# 01-ORIN_PWR.net
KiCad netlist of a schematic drawn in Altium Designer
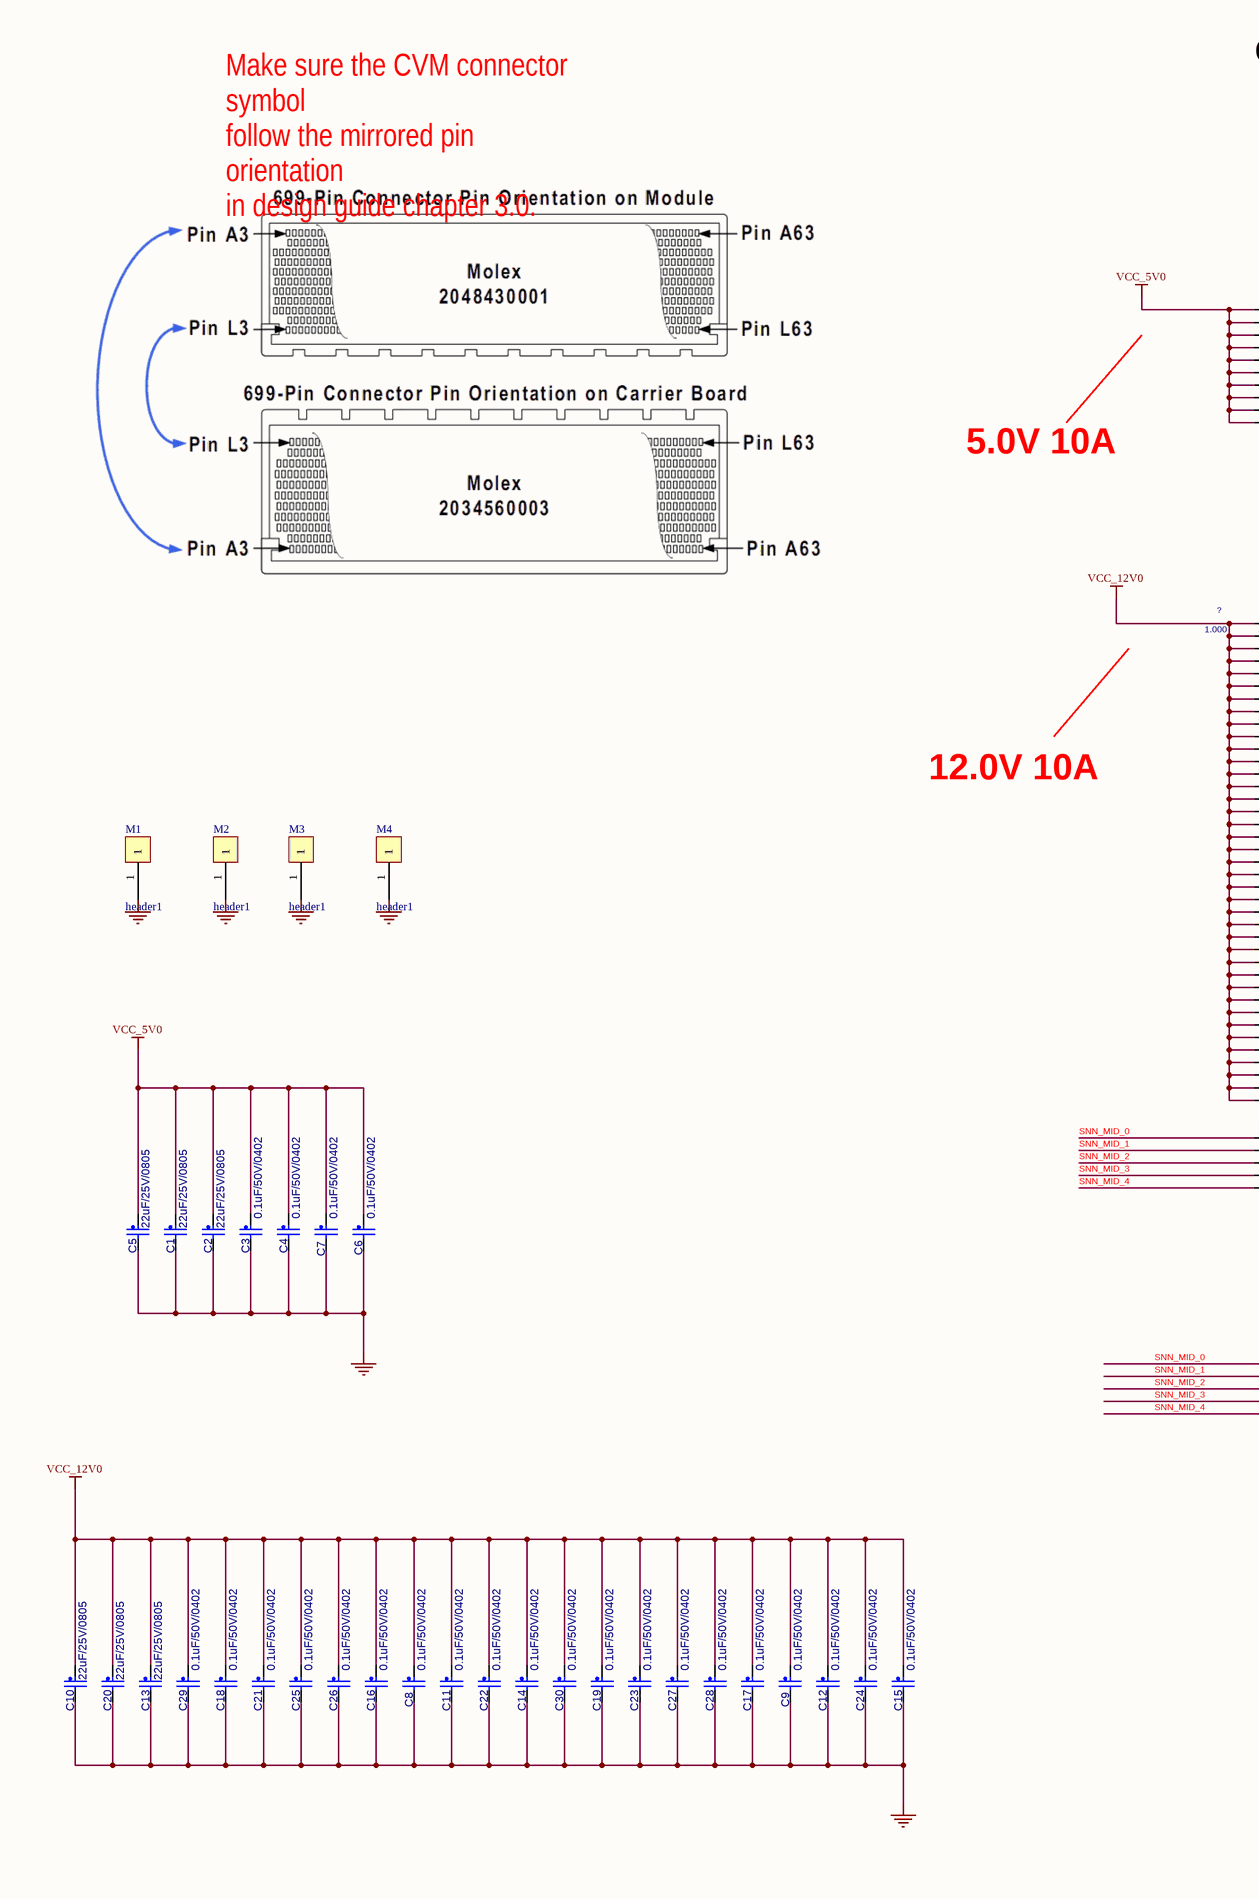
[diagram p0: 01-ORIN_PWR.SchDoc, left]
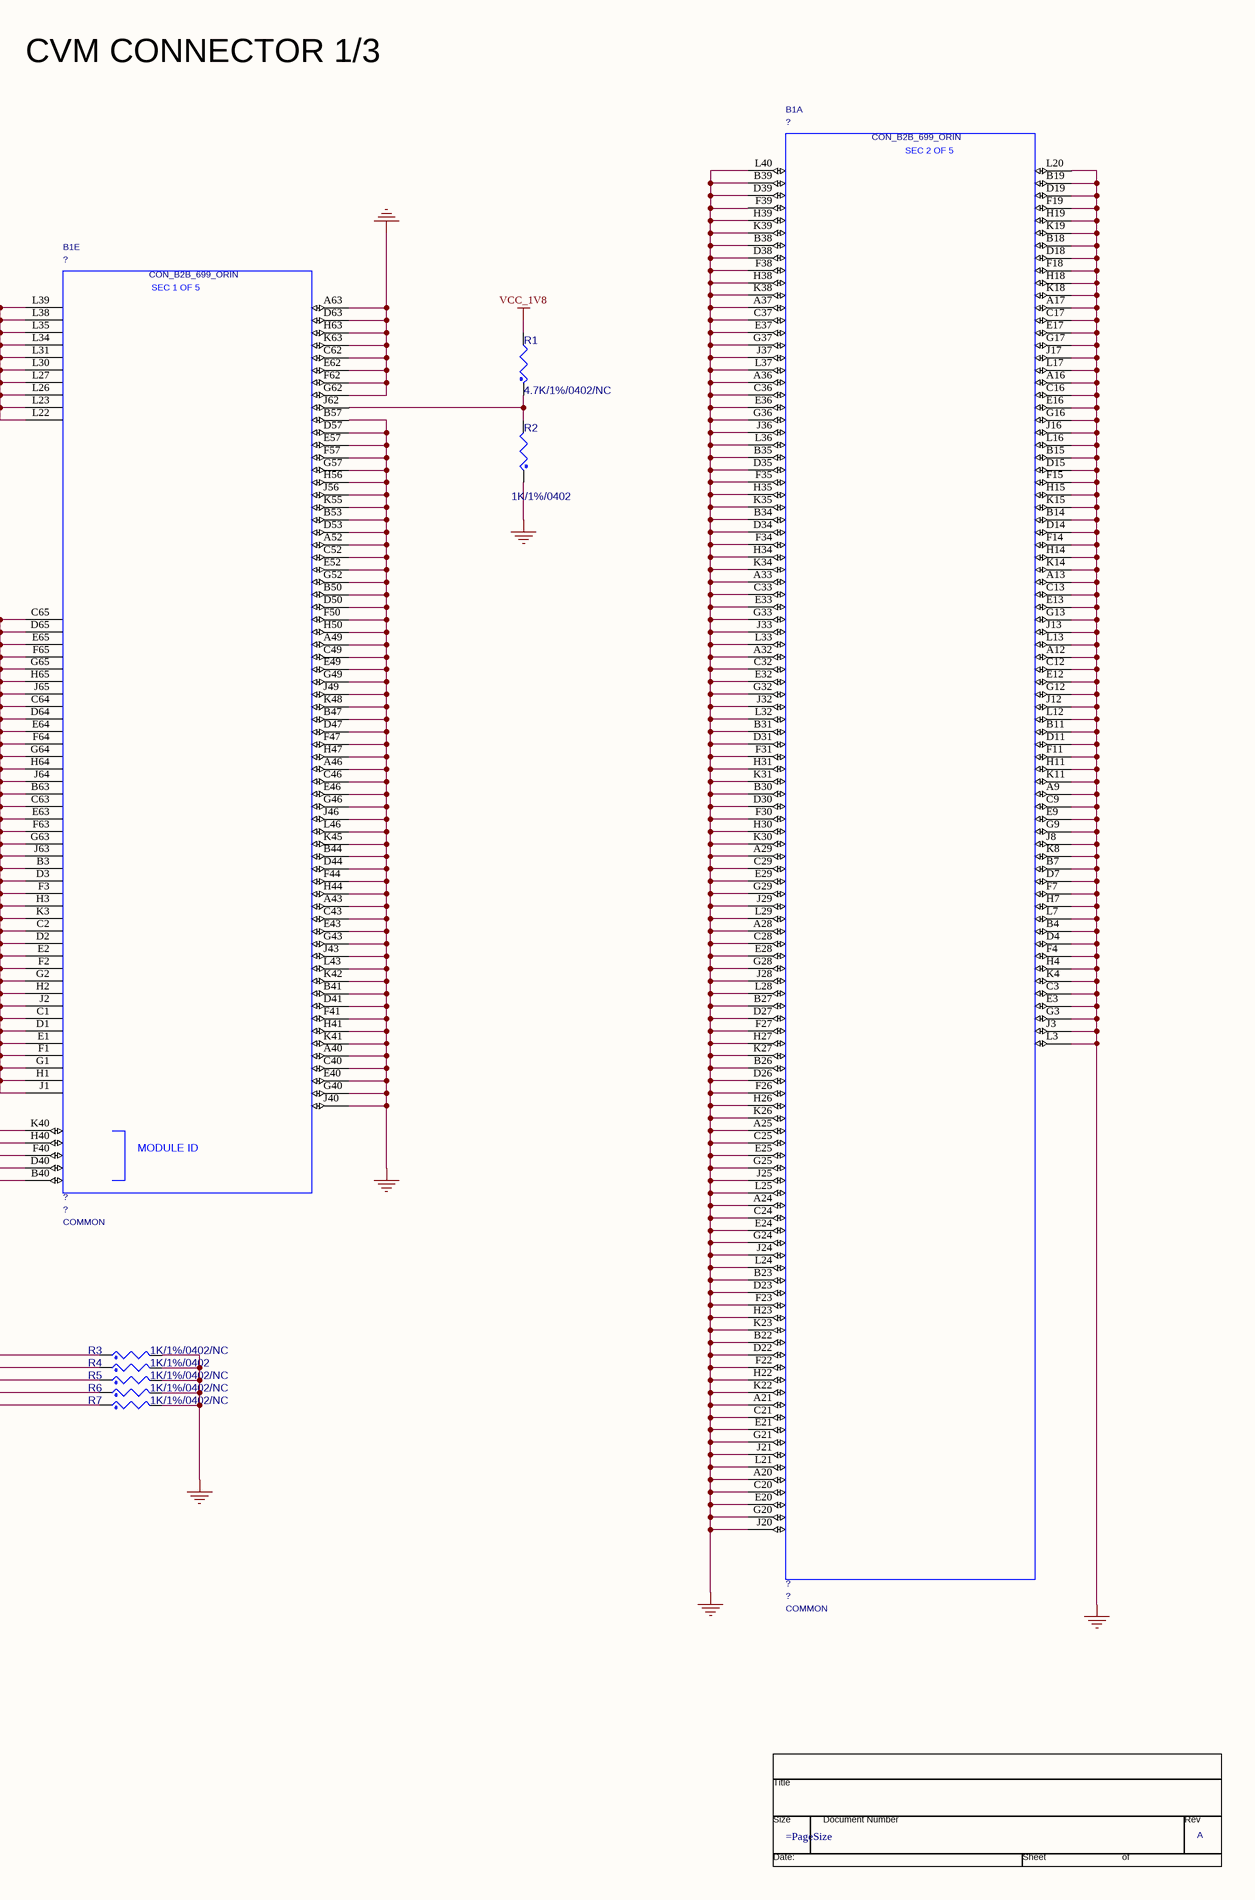
[diagram p1: 01-ORIN_PWR.SchDoc, right]

(export (version "E")
  (design (tool "Eeschema 10.0.6"))
  (components
    (comp (ref "B1")
      (value "CON_B2B_699_ORIN")
      (footprint "CON_MIRMEZ_699_BGA_ST_P009_P013_P015_REVERSE")
      (description "2034560003/MOLEX")
      (fields
        (field (name "DEVICE") "CON_B2B_699_ORIN")
        (field (name "NV_PN") "?")
        (field (name "PACK_TYPE") "?")
        (field (name "PATH") "?")
        (field (name "SKU") "COMMON")
      )
      (libsource (lib "*") (part "CON_B2B_699"))
    )
    (comp (ref "C1")
      (value "22uF/25V/0805")
      (footprint "C0805")
      (description "GRT31CC71E226ME13/MURATA")
      (fields (field (name "TOLERANCE") "10%") (field (name "VOLTAGE") "10v"))
      (libsource (lib "*") (part "CAP_NP"))
    )
    (comp (ref "C2")
      (value "22uF/25V/0805")
      (footprint "C0805")
      (description "GRT31CC71E226ME13/MURATA")
      (fields (field (name "VOLTAGE") "10v") (field (name "TOLERANCE") "10%"))
      (libsource (lib "*") (part "CAP_NP"))
    )
    (comp (ref "C3")
      (value "0.1uF/50V/0402")
      (footprint "C0402")
      (description "GCM155R71H104KE02/MURATA")
      (fields (field (name "VOLTAGE") "16V") (field (name "TOLERANCE") "10%"))
      (libsource (lib "*") (part "CAP_NP"))
    )
    (comp (ref "C4")
      (value "0.1uF/50V/0402")
      (footprint "C0402")
      (description "GCM155R71H104KE02/MURATA")
      (fields (field (name "TOLERANCE") "10%") (field (name "VOLTAGE") "16V"))
      (libsource (lib "*") (part "CAP_NP"))
    )
    (comp (ref "C5")
      (value "22uF/25V/0805")
      (footprint "C0805")
      (description "GRT31CC71E226ME13/MURATA")
      (fields (field (name "TOLERANCE") "10%") (field (name "VOLTAGE") "10v"))
      (libsource (lib "*") (part "CAP_NP"))
    )
    (comp (ref "C6")
      (value "0.1uF/50V/0402")
      (footprint "C0402")
      (description "GCM155R71H104KE02/MURATA")
      (fields (field (name "TOLERANCE") "10%") (field (name "VOLTAGE") "16V"))
      (libsource (lib "*") (part "CAP_NP"))
    )
    (comp (ref "C7")
      (value "0.1uF/50V/0402")
      (footprint "C0402")
      (description "GCM155R71H104KE02/MURATA")
      (fields (field (name "VOLTAGE") "16V") (field (name "TOLERANCE") "10%"))
      (libsource (lib "*") (part "CAP_NP"))
    )
    (comp (ref "C8")
      (value "0.1uF/50V/0402")
      (footprint "C0402")
      (description "GCM155R71H104KE02/MURATA")
      (fields (field (name "TOLERANCE") "10%") (field (name "VOLTAGE") "16V"))
      (libsource (lib "*") (part "CAP_NP"))
    )
    (comp (ref "C9")
      (value "0.1uF/50V/0402")
      (footprint "C0402")
      (description "GCM155R71H104KE02/MURATA")
      (fields (field (name "TOLERANCE") "10%") (field (name "VOLTAGE") "16V"))
      (libsource (lib "*") (part "CAP_NP"))
    )
    (comp (ref "C10")
      (value "22uF/25V/0805")
      (footprint "C0805")
      (description "GRT31CC71E226ME13/MURATA")
      (fields (field (name "VOLTAGE") "10v") (field (name "TOLERANCE") "10%"))
      (libsource (lib "*") (part "CAP_NP"))
    )
    (comp (ref "C11")
      (value "0.1uF/50V/0402")
      (footprint "C0402")
      (description "GCM155R71H104KE02/MURATA")
      (fields (field (name "VOLTAGE") "16V") (field (name "TOLERANCE") "10%"))
      (libsource (lib "*") (part "CAP_NP"))
    )
    (comp (ref "C12")
      (value "0.1uF/50V/0402")
      (footprint "C0402")
      (description "GCM155R71H104KE02/MURATA")
      (fields (field (name "VOLTAGE") "16V") (field (name "TOLERANCE") "10%"))
      (libsource (lib "*") (part "CAP_NP"))
    )
    (comp (ref "C13")
      (value "22uF/25V/0805")
      (footprint "C0805")
      (description "GRT31CC71E226ME13/MURATA")
      (fields (field (name "TOLERANCE") "10%") (field (name "VOLTAGE") "10v"))
      (libsource (lib "*") (part "CAP_NP"))
    )
    (comp (ref "C14")
      (value "0.1uF/50V/0402")
      (footprint "C0402")
      (description "GCM155R71H104KE02/MURATA")
      (fields (field (name "VOLTAGE") "16V") (field (name "TOLERANCE") "10%"))
      (libsource (lib "*") (part "CAP_NP"))
    )
    (comp (ref "C15")
      (value "0.1uF/50V/0402")
      (footprint "C0402")
      (description "GCM155R71H104KE02/MURATA")
      (fields (field (name "VOLTAGE") "16V") (field (name "TOLERANCE") "10%"))
      (libsource (lib "*") (part "CAP_NP"))
    )
    (comp (ref "C16")
      (value "0.1uF/50V/0402")
      (footprint "C0402")
      (description "GCM155R71H104KE02/MURATA")
      (fields (field (name "VOLTAGE") "16V") (field (name "TOLERANCE") "10%"))
      (libsource (lib "*") (part "CAP_NP"))
    )
    (comp (ref "C17")
      (value "0.1uF/50V/0402")
      (footprint "C0402")
      (description "GCM155R71H104KE02/MURATA")
      (fields (field (name "VOLTAGE") "16V") (field (name "TOLERANCE") "10%"))
      (libsource (lib "*") (part "CAP_NP"))
    )
    (comp (ref "C18")
      (value "0.1uF/50V/0402")
      (footprint "C0402")
      (description "GCM155R71H104KE02/MURATA")
      (fields (field (name "VOLTAGE") "16V") (field (name "TOLERANCE") "10%"))
      (libsource (lib "*") (part "CAP_NP"))
    )
    (comp (ref "C19")
      (value "0.1uF/50V/0402")
      (footprint "C0402")
      (description "GCM155R71H104KE02/MURATA")
      (fields (field (name "VOLTAGE") "16V") (field (name "TOLERANCE") "10%"))
      (libsource (lib "*") (part "CAP_NP"))
    )
    (comp (ref "C20")
      (value "22uF/25V/0805")
      (footprint "C0805")
      (description "GRT31CC71E226ME13/MURATA")
      (fields (field (name "VOLTAGE") "10v") (field (name "TOLERANCE") "10%"))
      (libsource (lib "*") (part "CAP_NP"))
    )
    (comp (ref "C21")
      (value "0.1uF/50V/0402")
      (footprint "C0402")
      (description "GCM155R71H104KE02/MURATA")
      (fields (field (name "TOLERANCE") "10%") (field (name "VOLTAGE") "16V"))
      (libsource (lib "*") (part "CAP_NP"))
    )
    (comp (ref "C22")
      (value "0.1uF/50V/0402")
      (footprint "C0402")
      (description "GCM155R71H104KE02/MURATA")
      (fields (field (name "TOLERANCE") "10%") (field (name "VOLTAGE") "16V"))
      (libsource (lib "*") (part "CAP_NP"))
    )
    (comp (ref "C23")
      (value "0.1uF/50V/0402")
      (footprint "C0402")
      (description "GCM155R71H104KE02/MURATA")
      (fields (field (name "TOLERANCE") "10%") (field (name "VOLTAGE") "16V"))
      (libsource (lib "*") (part "CAP_NP"))
    )
    (comp (ref "C24")
      (value "0.1uF/50V/0402")
      (footprint "C0402")
      (description "GCM155R71H104KE02/MURATA")
      (fields (field (name "TOLERANCE") "10%") (field (name "VOLTAGE") "16V"))
      (libsource (lib "*") (part "CAP_NP"))
    )
    (comp (ref "C25")
      (value "0.1uF/50V/0402")
      (footprint "C0402")
      (description "GCM155R71H104KE02/MURATA")
      (fields (field (name "VOLTAGE") "16V") (field (name "TOLERANCE") "10%"))
      (libsource (lib "*") (part "CAP_NP"))
    )
    (comp (ref "C26")
      (value "0.1uF/50V/0402")
      (footprint "C0402")
      (description "GCM155R71H104KE02/MURATA")
      (fields (field (name "TOLERANCE") "10%") (field (name "VOLTAGE") "16V"))
      (libsource (lib "*") (part "CAP_NP"))
    )
    (comp (ref "C27")
      (value "0.1uF/50V/0402")
      (footprint "C0402")
      (description "GCM155R71H104KE02/MURATA")
      (fields (field (name "VOLTAGE") "16V") (field (name "TOLERANCE") "10%"))
      (libsource (lib "*") (part "CAP_NP"))
    )
    (comp (ref "C28")
      (value "0.1uF/50V/0402")
      (footprint "C0402")
      (description "GCM155R71H104KE02/MURATA")
      (fields (field (name "TOLERANCE") "10%") (field (name "VOLTAGE") "16V"))
      (libsource (lib "*") (part "CAP_NP"))
    )
    (comp (ref "C29")
      (value "0.1uF/50V/0402")
      (footprint "C0402")
      (description "GCM155R71H104KE02/MURATA")
      (fields (field (name "TOLERANCE") "10%") (field (name "VOLTAGE") "16V"))
      (libsource (lib "*") (part "CAP_NP"))
    )
    (comp (ref "C30")
      (value "0.1uF/50V/0402")
      (footprint "C0402")
      (description "GCM155R71H104KE02/MURATA")
      (fields (field (name "TOLERANCE") "10%") (field (name "VOLTAGE") "16V"))
      (libsource (lib "*") (part "CAP_NP"))
    )
    (comp (ref "M1") (value "header1") (footprint "HOLE_M3_6.5") (libsource (lib "LIBS") (part "header1")))
    (comp (ref "M2") (value "header1") (footprint "HOLE_M3_6.5") (libsource (lib "LIBS") (part "header1")))
    (comp (ref "M3") (value "header1") (footprint "HOLE_M3_6.5") (libsource (lib "LIBS") (part "header1")))
    (comp (ref "M4") (value "header1") (footprint "HOLE_M3_6.5") (libsource (lib "LIBS") (part "header1")))
    (comp (ref "R1")
      (value "4.7K/1%/0402/NC")
      (footprint "R0402")
      (description "AC0402FR-074K7L/YAGEO")
      (fields (field (name "TOLERANCE") "5%") (field (name "Comment") "RES_Dup2"))
      (libsource (lib "*") (part "RES_Dup2"))
    )
    (comp (ref "R2")
      (value "1K/1%/0402")
      (footprint "R0402")
      (description "AC0402FR-071KL/YAGEO")
      (fields (field (name "TOLERANCE") "1%") (field (name "Comment") "RES_Dup2"))
      (libsource (lib "*") (part "RES_Dup2"))
    )
    (comp (ref "R3")
      (value "1K/1%/0402/NC")
      (footprint "R0402")
      (description "AC0402FR-071KL/YAGEO")
      (fields (field (name "TOLERANCE") "1%") (field (name "Comment") "RES_Dup2"))
      (libsource (lib "*") (part "RES_Dup2"))
    )
    (comp (ref "R4")
      (value "1K/1%/0402")
      (footprint "R0402")
      (description "AC0402FR-071KL/YAGEO")
      (fields (field (name "TOLERANCE") "1%") (field (name "Comment") "RES_Dup2"))
      (libsource (lib "*") (part "RES_Dup2"))
    )
    (comp (ref "R5")
      (value "1K/1%/0402/NC")
      (footprint "R0402")
      (description "AC0402FR-071KL/YAGEO")
      (fields (field (name "TOLERANCE") "1%") (field (name "Comment") "RES_Dup2"))
      (libsource (lib "*") (part "RES_Dup2"))
    )
    (comp (ref "R6")
      (value "1K/1%/0402/NC")
      (footprint "R0402")
      (description "AC0402FR-071KL/YAGEO")
      (fields (field (name "TOLERANCE") "1%") (field (name "Comment") "RES_Dup2"))
      (libsource (lib "*") (part "RES_Dup2"))
    )
    (comp (ref "R7")
      (value "1K/1%/0402/NC")
      (footprint "R0402")
      (description "AC0402FR-071KL/YAGEO")
      (fields (field (name "TOLERANCE") "1%") (field (name "Comment") "RES_Dup2"))
      (libsource (lib "*") (part "RES_Dup2"))
    )
  )
  (nets
    (net (code "1") (name "/SNN_MID_0") (class "Default")
      (node (ref "B1") (pin "K40") (pinfunction "MID0_K40") (pintype "bidirectional"))
      (node (ref "R3") (pin "1") (pinfunction "1_1") (pintype "passive"))
    )
    (net (code "2") (name "/SNN_MID_1") (class "Default")
      (node (ref "B1") (pin "H40") (pinfunction "MID1_H40") (pintype "bidirectional"))
      (node (ref "R4") (pin "1") (pinfunction "1_1") (pintype "passive"))
    )
    (net (code "3") (name "/SNN_MID_2") (class "Default")
      (node (ref "B1") (pin "F40") (pinfunction "MID2_F40") (pintype "bidirectional"))
      (node (ref "R5") (pin "1") (pinfunction "1_1") (pintype "passive"))
    )
    (net (code "4") (name "/SNN_MID_3") (class "Default")
      (node (ref "B1") (pin "D40") (pinfunction "MID3_D40") (pintype "bidirectional"))
      (node (ref "R6") (pin "1") (pinfunction "1_1") (pintype "passive"))
    )
    (net (code "5") (name "/SNN_MID_4") (class "Default")
      (node (ref "B1") (pin "B40") (pinfunction "MID4_B40") (pintype "bidirectional"))
      (node (ref "R7") (pin "1") (pinfunction "1_1") (pintype "passive"))
    )
    (net (code "6") (name "GND") (class "Default")
      (node (ref "B1") (pin "A12") (pinfunction "GND_215_A12") (pintype "bidirectional"))
      (node (ref "B1") (pin "A13") (pinfunction "GND_209_A13") (pintype "bidirectional"))
      (node (ref "B1") (pin "A16") (pinfunction "GND_193_A16") (pintype "bidirectional"))
      (node (ref "B1") (pin "A17") (pinfunction "GND_187_A17") (pintype "bidirectional"))
      (node (ref "B1") (pin "A20") (pinfunction "GND_171_A20") (pintype "bidirectional"))
      (node (ref "B1") (pin "A21") (pinfunction "GND_165_A21") (pintype "bidirectional"))
      (node (ref "B1") (pin "A24") (pinfunction "GND_149_A24") (pintype "bidirectional"))
      (node (ref "B1") (pin "A25") (pinfunction "GND_143_A25") (pintype "bidirectional"))
      (node (ref "B1") (pin "A28") (pinfunction "GND_127_A28") (pintype "bidirectional"))
      (node (ref "B1") (pin "A29") (pinfunction "GND_121_A29") (pintype "bidirectional"))
      (node (ref "B1") (pin "A32") (pinfunction "GND_105_A32") (pintype "bidirectional"))
      (node (ref "B1") (pin "A33") (pinfunction "GND_099_A33") (pintype "bidirectional"))
      (node (ref "B1") (pin "A36") (pinfunction "GND_083_A36") (pintype "bidirectional"))
      (node (ref "B1") (pin "A37") (pinfunction "GND_077_A37") (pintype "bidirectional"))
      (node (ref "B1") (pin "A40") (pinfunction "GND_061_A40") (pintype "bidirectional"))
      (node (ref "B1") (pin "A43") (pinfunction "GND_049_A43") (pintype "bidirectional"))
      (node (ref "B1") (pin "A46") (pinfunction "GND_038_A46") (pintype "bidirectional"))
      (node (ref "B1") (pin "A49") (pinfunction "GND_028_A49") (pintype "bidirectional"))
      (node (ref "B1") (pin "A52") (pinfunction "GND_020_A52") (pintype "bidirectional"))
      (node (ref "B1") (pin "A63") (pinfunction "GND_001_A63") (pintype "bidirectional"))
      (node (ref "B1") (pin "A9") (pinfunction "GND_226_A9") (pintype "bidirectional"))
      (node (ref "B1") (pin "B11") (pinfunction "GND_221_B11") (pintype "bidirectional"))
      (node (ref "B1") (pin "B14") (pinfunction "GND_204_B14") (pintype "bidirectional"))
      (node (ref "B1") (pin "B15") (pinfunction "GND_199_B15") (pintype "bidirectional"))
      (node (ref "B1") (pin "B18") (pinfunction "GND_182_B18") (pintype "bidirectional"))
      (node (ref "B1") (pin "B19") (pinfunction "GND_177_B19") (pintype "bidirectional"))
      (node (ref "B1") (pin "B22") (pinfunction "GND_160_B22") (pintype "bidirectional"))
      (node (ref "B1") (pin "B23") (pinfunction "GND_155_B23") (pintype "bidirectional"))
      (node (ref "B1") (pin "B26") (pinfunction "GND_138_B26") (pintype "bidirectional"))
      (node (ref "B1") (pin "B27") (pinfunction "GND_133_B27") (pintype "bidirectional"))
      (node (ref "B1") (pin "B30") (pinfunction "GND_116_B30") (pintype "bidirectional"))
      (node (ref "B1") (pin "B31") (pinfunction "GND_111_B31") (pintype "bidirectional"))
      (node (ref "B1") (pin "B34") (pinfunction "GND_094_B34") (pintype "bidirectional"))
      (node (ref "B1") (pin "B35") (pinfunction "GND_089_B35") (pintype "bidirectional"))
      (node (ref "B1") (pin "B38") (pinfunction "GND_072_B38") (pintype "bidirectional"))
      (node (ref "B1") (pin "B39") (pinfunction "GND_067_B39") (pintype "bidirectional"))
      (node (ref "B1") (pin "B4") (pinfunction "GND_237_B4") (pintype "bidirectional"))
      (node (ref "B1") (pin "B41") (pinfunction "GND_056_B41") (pintype "bidirectional"))
      (node (ref "B1") (pin "B44") (pinfunction "GND_045_B44") (pintype "bidirectional"))
      (node (ref "B1") (pin "B47") (pinfunction "GND_034_B47") (pintype "bidirectional"))
      (node (ref "B1") (pin "B50") (pinfunction "GND_024_B50") (pintype "bidirectional"))
      (node (ref "B1") (pin "B53") (pinfunction "GND_018_B53") (pintype "bidirectional"))
      (node (ref "B1") (pin "B57") (pinfunction "GND_010_B57") (pintype "bidirectional"))
      (node (ref "B1") (pin "B7") (pinfunction "GND_232_B7") (pintype "bidirectional"))
      (node (ref "B1") (pin "C12") (pinfunction "GND_216_C12") (pintype "bidirectional"))
      (node (ref "B1") (pin "C13") (pinfunction "GND_210_C13") (pintype "bidirectional"))
      (node (ref "B1") (pin "C16") (pinfunction "GND_194_C16") (pintype "bidirectional"))
      (node (ref "B1") (pin "C17") (pinfunction "GND_188_C17") (pintype "bidirectional"))
      (node (ref "B1") (pin "C20") (pinfunction "GND_172_C20") (pintype "bidirectional"))
      (node (ref "B1") (pin "C21") (pinfunction "GND_166_C21") (pintype "bidirectional"))
      (node (ref "B1") (pin "C24") (pinfunction "GND_150_C24") (pintype "bidirectional"))
      (node (ref "B1") (pin "C25") (pinfunction "GND_144_C25") (pintype "bidirectional"))
      (node (ref "B1") (pin "C28") (pinfunction "GND_128_C28") (pintype "bidirectional"))
      (node (ref "B1") (pin "C29") (pinfunction "GND_122_C29") (pintype "bidirectional"))
      (node (ref "B1") (pin "C3") (pinfunction "GND_242_C3") (pintype "bidirectional"))
      (node (ref "B1") (pin "C32") (pinfunction "GND_106_C32") (pintype "bidirectional"))
      (node (ref "B1") (pin "C33") (pinfunction "GND_100_C33") (pintype "bidirectional"))
      (node (ref "B1") (pin "C36") (pinfunction "GND_084_C36") (pintype "bidirectional"))
      (node (ref "B1") (pin "C37") (pinfunction "GND_078_C37") (pintype "bidirectional"))
      (node (ref "B1") (pin "C40") (pinfunction "GND_062_C40") (pintype "bidirectional"))
      (node (ref "B1") (pin "C43") (pinfunction "GND_050_C43") (pintype "bidirectional"))
      (node (ref "B1") (pin "C46") (pinfunction "GND_039_C46") (pintype "bidirectional"))
      (node (ref "B1") (pin "C49") (pinfunction "GND_029_C49") (pintype "bidirectional"))
      (node (ref "B1") (pin "C52") (pinfunction "GND_021_C52") (pintype "bidirectional"))
      (node (ref "B1") (pin "C62") (pinfunction "GND_005_C62") (pintype "bidirectional"))
      (node (ref "B1") (pin "C9") (pinfunction "GND_227_C9") (pintype "bidirectional"))
      (node (ref "B1") (pin "D11") (pinfunction "GND_222_D11") (pintype "bidirectional"))
      (node (ref "B1") (pin "D14") (pinfunction "GND_205_D14") (pintype "bidirectional"))
      (node (ref "B1") (pin "D15") (pinfunction "GND_200_D15") (pintype "bidirectional"))
      (node (ref "B1") (pin "D18") (pinfunction "GND_183_D18") (pintype "bidirectional"))
      (node (ref "B1") (pin "D19") (pinfunction "GND_178_D19") (pintype "bidirectional"))
      (node (ref "B1") (pin "D22") (pinfunction "GND_161_D22") (pintype "bidirectional"))
      (node (ref "B1") (pin "D23") (pinfunction "GND_156_D23") (pintype "bidirectional"))
      (node (ref "B1") (pin "D26") (pinfunction "GND_139_D26") (pintype "bidirectional"))
      (node (ref "B1") (pin "D27") (pinfunction "GND_134_D27") (pintype "bidirectional"))
      (node (ref "B1") (pin "D30") (pinfunction "GND_117_D30") (pintype "bidirectional"))
      (node (ref "B1") (pin "D31") (pinfunction "GND_112_D31") (pintype "bidirectional"))
      (node (ref "B1") (pin "D34") (pinfunction "GND_095_D34") (pintype "bidirectional"))
      (node (ref "B1") (pin "D35") (pinfunction "GND_090_D35") (pintype "bidirectional"))
      (node (ref "B1") (pin "D38") (pinfunction "GND_073_D38") (pintype "bidirectional"))
      (node (ref "B1") (pin "D39") (pinfunction "GND_068_D39") (pintype "bidirectional"))
      (node (ref "B1") (pin "D4") (pinfunction "GND_238_D4") (pintype "bidirectional"))
      (node (ref "B1") (pin "D41") (pinfunction "GND_057_D41") (pintype "bidirectional"))
      (node (ref "B1") (pin "D44") (pinfunction "GND_046_D44") (pintype "bidirectional"))
      (node (ref "B1") (pin "D47") (pinfunction "GND_035_D47") (pintype "bidirectional"))
      (node (ref "B1") (pin "D50") (pinfunction "GND_025_D50") (pintype "bidirectional"))
      (node (ref "B1") (pin "D53") (pinfunction "GND_019_D53") (pintype "bidirectional"))
      (node (ref "B1") (pin "D57") (pinfunction "GND_011_D57") (pintype "bidirectional"))
      (node (ref "B1") (pin "D63") (pinfunction "GND_002_D63") (pintype "bidirectional"))
      (node (ref "B1") (pin "D7") (pinfunction "GND_233_D7") (pintype "bidirectional"))
      (node (ref "B1") (pin "E12") (pinfunction "GND_217_E12") (pintype "bidirectional"))
      (node (ref "B1") (pin "E13") (pinfunction "GND_211_E13") (pintype "bidirectional"))
      (node (ref "B1") (pin "E16") (pinfunction "GND_195_E16") (pintype "bidirectional"))
      (node (ref "B1") (pin "E17") (pinfunction "GND_189_E17") (pintype "bidirectional"))
      (node (ref "B1") (pin "E20") (pinfunction "GND_173_E20") (pintype "bidirectional"))
      (node (ref "B1") (pin "E21") (pinfunction "GND_167_E21") (pintype "bidirectional"))
      (node (ref "B1") (pin "E24") (pinfunction "GND_151_E24") (pintype "bidirectional"))
      (node (ref "B1") (pin "E25") (pinfunction "GND_145_E25") (pintype "bidirectional"))
      (node (ref "B1") (pin "E28") (pinfunction "GND_129_E28") (pintype "bidirectional"))
      (node (ref "B1") (pin "E29") (pinfunction "GND_123_E29") (pintype "bidirectional"))
      (node (ref "B1") (pin "E3") (pinfunction "GND_243_E3") (pintype "bidirectional"))
      (node (ref "B1") (pin "E32") (pinfunction "GND_107_E32") (pintype "bidirectional"))
      (node (ref "B1") (pin "E33") (pinfunction "GND_101_E33") (pintype "bidirectional"))
      (node (ref "B1") (pin "E36") (pinfunction "GND_085_E36") (pintype "bidirectional"))
      (node (ref "B1") (pin "E37") (pinfunction "GND_079_E37") (pintype "bidirectional"))
      (node (ref "B1") (pin "E40") (pinfunction "GND_063_E40") (pintype "bidirectional"))
      (node (ref "B1") (pin "E43") (pinfunction "GND_051_E43") (pintype "bidirectional"))
      (node (ref "B1") (pin "E46") (pinfunction "GND_040_E46") (pintype "bidirectional"))
      (node (ref "B1") (pin "E49") (pinfunction "GND_030_E49") (pintype "bidirectional"))
      (node (ref "B1") (pin "E52") (pinfunction "GND_022_E52") (pintype "bidirectional"))
      (node (ref "B1") (pin "E57") (pinfunction "GND_012_E57") (pintype "bidirectional"))
      (node (ref "B1") (pin "E62") (pinfunction "GND_006_E62") (pintype "bidirectional"))
      (node (ref "B1") (pin "E9") (pinfunction "GND_228_E9") (pintype "bidirectional"))
      (node (ref "B1") (pin "F11") (pinfunction "GND_223_F11") (pintype "bidirectional"))
      (node (ref "B1") (pin "F14") (pinfunction "GND_206_F14") (pintype "bidirectional"))
      (node (ref "B1") (pin "F15") (pinfunction "GND_201_F15") (pintype "bidirectional"))
      (node (ref "B1") (pin "F18") (pinfunction "GND_184_F18") (pintype "bidirectional"))
      (node (ref "B1") (pin "F19") (pinfunction "GND_179_F19") (pintype "bidirectional"))
      (node (ref "B1") (pin "F22") (pinfunction "GND_162_F22") (pintype "bidirectional"))
      (node (ref "B1") (pin "F23") (pinfunction "GND_157_F23") (pintype "bidirectional"))
      (node (ref "B1") (pin "F26") (pinfunction "GND_140_F26") (pintype "bidirectional"))
      (node (ref "B1") (pin "F27") (pinfunction "GND_135_F27") (pintype "bidirectional"))
      (node (ref "B1") (pin "F30") (pinfunction "GND_118_F30") (pintype "bidirectional"))
      (node (ref "B1") (pin "F31") (pinfunction "GND_113_F31") (pintype "bidirectional"))
      (node (ref "B1") (pin "F34") (pinfunction "GND_096_F34") (pintype "bidirectional"))
      (node (ref "B1") (pin "F35") (pinfunction "GND_091_F35") (pintype "bidirectional"))
      (node (ref "B1") (pin "F38") (pinfunction "GND_074_F38") (pintype "bidirectional"))
      (node (ref "B1") (pin "F39") (pinfunction "GND_069_F39") (pintype "bidirectional"))
      (node (ref "B1") (pin "F4") (pinfunction "GND_239_F4") (pintype "bidirectional"))
      (node (ref "B1") (pin "F41") (pinfunction "GND_058_F41") (pintype "bidirectional"))
      (node (ref "B1") (pin "F44") (pinfunction "GND_047_F44") (pintype "bidirectional"))
      (node (ref "B1") (pin "F47") (pinfunction "GND_036_F47") (pintype "bidirectional"))
      (node (ref "B1") (pin "F50") (pinfunction "GND_026_F50") (pintype "bidirectional"))
      (node (ref "B1") (pin "F57") (pinfunction "GND_013_F57") (pintype "bidirectional"))
      (node (ref "B1") (pin "F62") (pinfunction "GND_007_F62") (pintype "bidirectional"))
      (node (ref "B1") (pin "F7") (pinfunction "GND_234_F7") (pintype "bidirectional"))
      (node (ref "B1") (pin "G12") (pinfunction "GND_218_G12") (pintype "bidirectional"))
      (node (ref "B1") (pin "G13") (pinfunction "GND_212_G13") (pintype "bidirectional"))
      (node (ref "B1") (pin "G16") (pinfunction "GND_196_G16") (pintype "bidirectional"))
      (node (ref "B1") (pin "G17") (pinfunction "GND_190_G17") (pintype "bidirectional"))
      (node (ref "B1") (pin "G20") (pinfunction "GND_174_G20") (pintype "bidirectional"))
      (node (ref "B1") (pin "G21") (pinfunction "GND_168_G21") (pintype "bidirectional"))
      (node (ref "B1") (pin "G24") (pinfunction "GND_152_G24") (pintype "bidirectional"))
      (node (ref "B1") (pin "G25") (pinfunction "GND_146_G25") (pintype "bidirectional"))
      (node (ref "B1") (pin "G28") (pinfunction "GND_130_G28") (pintype "bidirectional"))
      (node (ref "B1") (pin "G29") (pinfunction "GND_124_G29") (pintype "bidirectional"))
      (node (ref "B1") (pin "G3") (pinfunction "GND_244_G3") (pintype "bidirectional"))
      (node (ref "B1") (pin "G32") (pinfunction "GND_108_G32") (pintype "bidirectional"))
      (node (ref "B1") (pin "G33") (pinfunction "GND_102_G33") (pintype "bidirectional"))
      (node (ref "B1") (pin "G36") (pinfunction "GND_086_G36") (pintype "bidirectional"))
      (node (ref "B1") (pin "G37") (pinfunction "GND_080_G37") (pintype "bidirectional"))
      (node (ref "B1") (pin "G40") (pinfunction "GND_064_G40") (pintype "bidirectional"))
      (node (ref "B1") (pin "G43") (pinfunction "GND_052_G43") (pintype "bidirectional"))
      (node (ref "B1") (pin "G46") (pinfunction "GND_041_G46") (pintype "bidirectional"))
      (node (ref "B1") (pin "G49") (pinfunction "GND_031_G49") (pintype "bidirectional"))
      (node (ref "B1") (pin "G52") (pinfunction "GND_023_G52") (pintype "bidirectional"))
      (node (ref "B1") (pin "G57") (pinfunction "GND_014_G57") (pintype "bidirectional"))
      (node (ref "B1") (pin "G62") (pinfunction "GND_008_G62") (pintype "bidirectional"))
      (node (ref "B1") (pin "G9") (pinfunction "GND_229_G9") (pintype "bidirectional"))
      (node (ref "B1") (pin "H11") (pinfunction "GND_224_H11") (pintype "bidirectional"))
      (node (ref "B1") (pin "H14") (pinfunction "GND_207_H14") (pintype "bidirectional"))
      (node (ref "B1") (pin "H15") (pinfunction "GND_202_H15") (pintype "bidirectional"))
      (node (ref "B1") (pin "H18") (pinfunction "GND_185_H18") (pintype "bidirectional"))
      (node (ref "B1") (pin "H19") (pinfunction "GND_180_H19") (pintype "bidirectional"))
      (node (ref "B1") (pin "H22") (pinfunction "GND_163_H22") (pintype "bidirectional"))
      (node (ref "B1") (pin "H23") (pinfunction "GND_158_H23") (pintype "bidirectional"))
      (node (ref "B1") (pin "H26") (pinfunction "GND_141_H26") (pintype "bidirectional"))
      (node (ref "B1") (pin "H27") (pinfunction "GND_136_H27") (pintype "bidirectional"))
      (node (ref "B1") (pin "H30") (pinfunction "GND_119_H30") (pintype "bidirectional"))
      (node (ref "B1") (pin "H31") (pinfunction "GND_114_H31") (pintype "bidirectional"))
      (node (ref "B1") (pin "H34") (pinfunction "GND_097_H34") (pintype "bidirectional"))
      (node (ref "B1") (pin "H35") (pinfunction "GND_092_H35") (pintype "bidirectional"))
      (node (ref "B1") (pin "H38") (pinfunction "GND_075_H38") (pintype "bidirectional"))
      (node (ref "B1") (pin "H39") (pinfunction "GND_070_H39") (pintype "bidirectional"))
      (node (ref "B1") (pin "H4") (pinfunction "GND_240_H4") (pintype "bidirectional"))
      (node (ref "B1") (pin "H41") (pinfunction "GND_059_H41") (pintype "bidirectional"))
      (node (ref "B1") (pin "H44") (pinfunction "GND_048_H44") (pintype "bidirectional"))
      (node (ref "B1") (pin "H47") (pinfunction "GND_037_H47") (pintype "bidirectional"))
      (node (ref "B1") (pin "H50") (pinfunction "GND_027_H50") (pintype "bidirectional"))
      (node (ref "B1") (pin "H56") (pinfunction "GND_015_H56") (pintype "bidirectional"))
      (node (ref "B1") (pin "H63") (pinfunction "GND_003_H63") (pintype "bidirectional"))
      (node (ref "B1") (pin "H7") (pinfunction "GND_235_H7") (pintype "bidirectional"))
      (node (ref "B1") (pin "J12") (pinfunction "GND_219_J12") (pintype "bidirectional"))
      (node (ref "B1") (pin "J13") (pinfunction "GND_213_J13") (pintype "bidirectional"))
      (node (ref "B1") (pin "J16") (pinfunction "GND_197_J16") (pintype "bidirectional"))
      (node (ref "B1") (pin "J17") (pinfunction "GND_191_J17") (pintype "bidirectional"))
      (node (ref "B1") (pin "J20") (pinfunction "GND_175_J20") (pintype "bidirectional"))
      (node (ref "B1") (pin "J21") (pinfunction "GND_169_J21") (pintype "bidirectional"))
      (node (ref "B1") (pin "J24") (pinfunction "GND_153_J24") (pintype "bidirectional"))
      (node (ref "B1") (pin "J25") (pinfunction "GND_147_J25") (pintype "bidirectional"))
      (node (ref "B1") (pin "J28") (pinfunction "GND_131_J28") (pintype "bidirectional"))
      (node (ref "B1") (pin "J29") (pinfunction "GND_125_J29") (pintype "bidirectional"))
      (node (ref "B1") (pin "J3") (pinfunction "GND_245_J3") (pintype "bidirectional"))
      (node (ref "B1") (pin "J32") (pinfunction "GND_109_J32") (pintype "bidirectional"))
      (node (ref "B1") (pin "J33") (pinfunction "GND_103_J33") (pintype "bidirectional"))
      (node (ref "B1") (pin "J36") (pinfunction "GND_087_J36") (pintype "bidirectional"))
      (node (ref "B1") (pin "J37") (pinfunction "GND_081_J37") (pintype "bidirectional"))
      (node (ref "B1") (pin "J40") (pinfunction "GND_065_J40") (pintype "bidirectional"))
      (node (ref "B1") (pin "J43") (pinfunction "GND_053_J43") (pintype "bidirectional"))
      (node (ref "B1") (pin "J46") (pinfunction "GND_042_J46") (pintype "bidirectional"))
      (node (ref "B1") (pin "J49") (pinfunction "GND_032_J49") (pintype "bidirectional"))
      (node (ref "B1") (pin "J56") (pinfunction "GND_016_J56") (pintype "bidirectional"))
      (node (ref "B1") (pin "J8") (pinfunction "GND_230_J8") (pintype "bidirectional"))
      (node (ref "B1") (pin "K11") (pinfunction "GND_225_K11") (pintype "bidirectional"))
      (node (ref "B1") (pin "K14") (pinfunction "GND_208_K14") (pintype "bidirectional"))
      (node (ref "B1") (pin "K15") (pinfunction "GND_203_K15") (pintype "bidirectional"))
      (node (ref "B1") (pin "K18") (pinfunction "GND_186_K18") (pintype "bidirectional"))
      (node (ref "B1") (pin "K19") (pinfunction "GND_181_K19") (pintype "bidirectional"))
      (node (ref "B1") (pin "K22") (pinfunction "GND_164_K22") (pintype "bidirectional"))
      (node (ref "B1") (pin "K23") (pinfunction "GND_159_K23") (pintype "bidirectional"))
      (node (ref "B1") (pin "K26") (pinfunction "GND_142_K26") (pintype "bidirectional"))
      (node (ref "B1") (pin "K27") (pinfunction "GND_137_K27") (pintype "bidirectional"))
      (node (ref "B1") (pin "K30") (pinfunction "GND_120_K30") (pintype "bidirectional"))
      (node (ref "B1") (pin "K31") (pinfunction "GND_115_K31") (pintype "bidirectional"))
      (node (ref "B1") (pin "K34") (pinfunction "GND_098_K34") (pintype "bidirectional"))
      (node (ref "B1") (pin "K35") (pinfunction "GND_093_K35") (pintype "bidirectional"))
      (node (ref "B1") (pin "K38") (pinfunction "GND_076_K38") (pintype "bidirectional"))
      (node (ref "B1") (pin "K39") (pinfunction "GND_071_K39") (pintype "bidirectional"))
      (node (ref "B1") (pin "K4") (pinfunction "GND_241_K4") (pintype "bidirectional"))
      (node (ref "B1") (pin "K41") (pinfunction "GND_060_K41") (pintype "bidirectional"))
      (node (ref "B1") (pin "K42") (pinfunction "GND_055_K42") (pintype "bidirectional"))
      (node (ref "B1") (pin "K45") (pinfunction "GND_044_K45") (pintype "bidirectional"))
      (node (ref "B1") (pin "K48") (pinfunction "GND_033_K48") (pintype "bidirectional"))
      (node (ref "B1") (pin "K55") (pinfunction "GND_017_K55") (pintype "bidirectional"))
      (node (ref "B1") (pin "K63") (pinfunction "GND_004_K63") (pintype "bidirectional"))
      (node (ref "B1") (pin "K8") (pinfunction "GND_231_K8") (pintype "bidirectional"))
      (node (ref "B1") (pin "L12") (pinfunction "GND_220_L12") (pintype "bidirectional"))
      (node (ref "B1") (pin "L13") (pinfunction "GND_214_L13") (pintype "bidirectional"))
      (node (ref "B1") (pin "L16") (pinfunction "GND_198_L16") (pintype "bidirectional"))
      (node (ref "B1") (pin "L17") (pinfunction "GND_192_L17") (pintype "bidirectional"))
      (node (ref "B1") (pin "L20") (pinfunction "GND_176_L20") (pintype "bidirectional"))
      (node (ref "B1") (pin "L21") (pinfunction "GND_170_L21") (pintype "bidirectional"))
      (node (ref "B1") (pin "L24") (pinfunction "GND_154_L24") (pintype "bidirectional"))
      (node (ref "B1") (pin "L25") (pinfunction "GND_148_L25") (pintype "bidirectional"))
      (node (ref "B1") (pin "L28") (pinfunction "GND_132_L28") (pintype "bidirectional"))
      (node (ref "B1") (pin "L29") (pinfunction "GND_126_L29") (pintype "bidirectional"))
      (node (ref "B1") (pin "L3") (pinfunction "GND_246_L3") (pintype "bidirectional"))
      (node (ref "B1") (pin "L32") (pinfunction "GND_110_L32") (pintype "bidirectional"))
      (node (ref "B1") (pin "L33") (pinfunction "GND_104_L33") (pintype "bidirectional"))
      (node (ref "B1") (pin "L36") (pinfunction "GND_088_L36") (pintype "bidirectional"))
      (node (ref "B1") (pin "L37") (pinfunction "GND_082_L37") (pintype "bidirectional"))
      (node (ref "B1") (pin "L40") (pinfunction "GND_066_L40") (pintype "bidirectional"))
      (node (ref "B1") (pin "L43") (pinfunction "GND_054_L43") (pintype "bidirectional"))
      (node (ref "B1") (pin "L46") (pinfunction "GND_043_L46") (pintype "bidirectional"))
      (node (ref "B1") (pin "L7") (pinfunction "GND_236_L7") (pintype "bidirectional"))
      (node (ref "C1") (pin "2") (pinfunction "2_2") (pintype "passive"))
      (node (ref "C10") (pin "2") (pinfunction "2_2") (pintype "passive"))
      (node (ref "C11") (pin "2") (pinfunction "2_2") (pintype "passive"))
      (node (ref "C12") (pin "2") (pinfunction "2_2") (pintype "passive"))
      (node (ref "C13") (pin "2") (pinfunction "2_2") (pintype "passive"))
      (node (ref "C14") (pin "2") (pinfunction "2_2") (pintype "passive"))
      (node (ref "C15") (pin "2") (pinfunction "2_2") (pintype "passive"))
      (node (ref "C16") (pin "2") (pinfunction "2_2") (pintype "passive"))
      (node (ref "C17") (pin "2") (pinfunction "2_2") (pintype "passive"))
      (node (ref "C18") (pin "2") (pinfunction "2_2") (pintype "passive"))
      (node (ref "C19") (pin "2") (pinfunction "2_2") (pintype "passive"))
      (node (ref "C2") (pin "2") (pinfunction "2_2") (pintype "passive"))
      (node (ref "C20") (pin "2") (pinfunction "2_2") (pintype "passive"))
      (node (ref "C21") (pin "2") (pinfunction "2_2") (pintype "passive"))
      (node (ref "C22") (pin "2") (pinfunction "2_2") (pintype "passive"))
      (node (ref "C23") (pin "2") (pinfunction "2_2") (pintype "passive"))
      (node (ref "C24") (pin "2") (pinfunction "2_2") (pintype "passive"))
      (node (ref "C25") (pin "2") (pinfunction "2_2") (pintype "passive"))
      (node (ref "C26") (pin "2") (pinfunction "2_2") (pintype "passive"))
      (node (ref "C27") (pin "2") (pinfunction "2_2") (pintype "passive"))
      (node (ref "C28") (pin "2") (pinfunction "2_2") (pintype "passive"))
      (node (ref "C29") (pin "2") (pinfunction "2_2") (pintype "passive"))
      (node (ref "C3") (pin "2") (pinfunction "2_2") (pintype "passive"))
      (node (ref "C30") (pin "2") (pinfunction "2_2") (pintype "passive"))
      (node (ref "C4") (pin "2") (pinfunction "2_2") (pintype "passive"))
      (node (ref "C5") (pin "2") (pinfunction "2_2") (pintype "passive"))
      (node (ref "C6") (pin "2") (pinfunction "2_2") (pintype "passive"))
      (node (ref "C7") (pin "2") (pinfunction "2_2") (pintype "passive"))
      (node (ref "C8") (pin "2") (pinfunction "2_2") (pintype "passive"))
      (node (ref "C9") (pin "2") (pinfunction "2_2") (pintype "passive"))
      (node (ref "M1") (pin "1") (pinfunction "1_1") (pintype "passive"))
      (node (ref "M2") (pin "1") (pinfunction "1_1") (pintype "passive"))
      (node (ref "M3") (pin "1") (pinfunction "1_1") (pintype "passive"))
      (node (ref "M4") (pin "1") (pinfunction "1_1") (pintype "passive"))
      (node (ref "R2") (pin "1") (pinfunction "1_1") (pintype "passive"))
      (node (ref "R3") (pin "2") (pinfunction "2_2") (pintype "passive"))
      (node (ref "R4") (pin "2") (pinfunction "2_2") (pintype "passive"))
      (node (ref "R5") (pin "2") (pinfunction "2_2") (pintype "passive"))
      (node (ref "R6") (pin "2") (pinfunction "2_2") (pintype "passive"))
      (node (ref "R7") (pin "2") (pinfunction "2_2") (pintype "passive"))
    )
    (net (code "7") (name "Net-(B1E-GND_009)") (class "Default")
      (node (ref "B1") (pin "J62") (pinfunction "GND_009_J62") (pintype "bidirectional"))
      (node (ref "R1") (pin "1") (pinfunction "1_1") (pintype "passive"))
      (node (ref "R2") (pin "2") (pinfunction "2_2") (pintype "passive"))
    )
    (net (code "8") (name "VCC_1V8") (class "Default")
      (node (ref "R1") (pin "2") (pinfunction "2_2") (pintype "passive"))
    )
    (net (code "9") (name "VCC_5V0") (class "Default")
      (node (ref "B1") (pin "L22") (pinfunction "SYS_VIN_MV_10_L22") (pintype "power_in"))
      (node (ref "B1") (pin "L23") (pinfunction "SYS_VIN_MV_09_L23") (pintype "power_in"))
      (node (ref "B1") (pin "L26") (pinfunction "SYS_VIN_MV_08_L26") (pintype "power_in"))
      (node (ref "B1") (pin "L27") (pinfunction "SYS_VIN_MV_07_L27") (pintype "power_in"))
      (node (ref "B1") (pin "L30") (pinfunction "SYS_VIN_MV_06_L30") (pintype "power_in"))
      (node (ref "B1") (pin "L31") (pinfunction "SYS_VIN_MV_05_L31") (pintype "power_in"))
      (node (ref "B1") (pin "L34") (pinfunction "SYS_VIN_MV_04_L34") (pintype "power_in"))
      (node (ref "B1") (pin "L35") (pinfunction "SYS_VIN_MV_03_L35") (pintype "power_in"))
      (node (ref "B1") (pin "L38") (pinfunction "SYS_VIN_MV_02_L38") (pintype "power_in"))
      (node (ref "B1") (pin "L39") (pinfunction "SYS_VIN_MV_01_L39") (pintype "power_in"))
      (node (ref "C1") (pin "1") (pinfunction "1_1") (pintype "passive"))
      (node (ref "C2") (pin "1") (pinfunction "1_1") (pintype "passive"))
      (node (ref "C3") (pin "1") (pinfunction "1_1") (pintype "passive"))
      (node (ref "C4") (pin "1") (pinfunction "1_1") (pintype "passive"))
      (node (ref "C5") (pin "1") (pinfunction "1_1") (pintype "passive"))
      (node (ref "C6") (pin "1") (pinfunction "1_1") (pintype "passive"))
      (node (ref "C7") (pin "1") (pinfunction "1_1") (pintype "passive"))
    )
    (net (code "10") (name "VCC_12V0") (class "Default")
      (node (ref "B1") (pin "B3") (pinfunction "SYS_VIN_HV_21_B3") (pintype "power_in"))
      (node (ref "B1") (pin "B63") (pinfunction "SYS_VIN_HV_15_B63") (pintype "power_in"))
      (node (ref "B1") (pin "C1") (pinfunction "SYS_VIN_HV_33_C1") (pintype "power_in"))
      (node (ref "B1") (pin "C2") (pinfunction "SYS_VIN_HV_26_C2") (pintype "power_in"))
      (node (ref "B1") (pin "C63") (pinfunction "SYS_VIN_HV_16_C63") (pintype "power_in"))
      (node (ref "B1") (pin "C64") (pinfunction "SYS_VIN_HV_08_C64") (pintype "power_in"))
      (node (ref "B1") (pin "C65") (pinfunction "SYS_VIN_HV_01_C65") (pintype "power_in"))
      (node (ref "B1") (pin "D1") (pinfunction "SYS_VIN_HV_34_D1") (pintype "power_in"))
      (node (ref "B1") (pin "D2") (pinfunction "SYS_VIN_HV_27_D2") (pintype "power_in"))
      (node (ref "B1") (pin "D3") (pinfunction "SYS_VIN_HV_22_D3") (pintype "power_in"))
      (node (ref "B1") (pin "D64") (pinfunction "SYS_VIN_HV_09_D64") (pintype "power_in"))
      (node (ref "B1") (pin "D65") (pinfunction "SYS_VIN_HV_02_D65") (pintype "power_in"))
      (node (ref "B1") (pin "E1") (pinfunction "SYS_VIN_HV_35_E1") (pintype "power_in"))
      (node (ref "B1") (pin "E2") (pinfunction "SYS_VIN_HV_28_E2") (pintype "power_in"))
      (node (ref "B1") (pin "E63") (pinfunction "SYS_VIN_HV_17_E63") (pintype "power_in"))
      (node (ref "B1") (pin "E64") (pinfunction "SYS_VIN_HV_10_E64") (pintype "power_in"))
      (node (ref "B1") (pin "E65") (pinfunction "SYS_VIN_HV_03_E65") (pintype "power_in"))
      (node (ref "B1") (pin "F1") (pinfunction "SYS_VIN_HV_36_F1") (pintype "power_in"))
      (node (ref "B1") (pin "F2") (pinfunction "SYS_VIN_HV_29_F2") (pintype "power_in"))
      (node (ref "B1") (pin "F3") (pinfunction "SYS_VIN_HV_23_F3") (pintype "power_in"))
      (node (ref "B1") (pin "F63") (pinfunction "SYS_VIN_HV_18_F63") (pintype "power_in"))
      (node (ref "B1") (pin "F64") (pinfunction "SYS_VIN_HV_11_F64") (pintype "power_in"))
      (node (ref "B1") (pin "F65") (pinfunction "SYS_VIN_HV_04_F65") (pintype "power_in"))
      (node (ref "B1") (pin "G1") (pinfunction "SYS_VIN_HV_37_G1") (pintype "power_in"))
      (node (ref "B1") (pin "G2") (pinfunction "SYS_VIN_HV_30_G2") (pintype "power_in"))
      (node (ref "B1") (pin "G63") (pinfunction "SYS_VIN_HV_19_G63") (pintype "power_in"))
      (node (ref "B1") (pin "G64") (pinfunction "SYS_VIN_HV_12_G64") (pintype "power_in"))
      (node (ref "B1") (pin "G65") (pinfunction "SYS_VIN_HV_05_G65") (pintype "power_in"))
      (node (ref "B1") (pin "H1") (pinfunction "SYS_VIN_HV_38_H1") (pintype "power_in"))
      (node (ref "B1") (pin "H2") (pinfunction "SYS_VIN_HV_31_H2") (pintype "power_in"))
      (node (ref "B1") (pin "H3") (pinfunction "SYS_VIN_HV_24_H3") (pintype "power_in"))
      (node (ref "B1") (pin "H64") (pinfunction "SYS_VIN_HV_13_H64") (pintype "power_in"))
      (node (ref "B1") (pin "H65") (pinfunction "SYS_VIN_HV_06_H65") (pintype "power_in"))
      (node (ref "B1") (pin "J1") (pinfunction "SYS_VIN_HV_39_J1") (pintype "power_in"))
      (node (ref "B1") (pin "J2") (pinfunction "SYS_VIN_HV_32_J2") (pintype "power_in"))
      (node (ref "B1") (pin "J63") (pinfunction "SYS_VIN_HV_20_J63") (pintype "power_in"))
      (node (ref "B1") (pin "J64") (pinfunction "SYS_VIN_HV_14_J64") (pintype "power_in"))
      (node (ref "B1") (pin "J65") (pinfunction "SYS_VIN_HV_07_J65") (pintype "power_in"))
      (node (ref "B1") (pin "K3") (pinfunction "SYS_VIN_HV_25_K3") (pintype "power_in"))
      (node (ref "C10") (pin "1") (pinfunction "1_1") (pintype "passive"))
      (node (ref "C11") (pin "1") (pinfunction "1_1") (pintype "passive"))
      (node (ref "C12") (pin "1") (pinfunction "1_1") (pintype "passive"))
      (node (ref "C13") (pin "1") (pinfunction "1_1") (pintype "passive"))
      (node (ref "C14") (pin "1") (pinfunction "1_1") (pintype "passive"))
      (node (ref "C15") (pin "1") (pinfunction "1_1") (pintype "passive"))
      (node (ref "C16") (pin "1") (pinfunction "1_1") (pintype "passive"))
      (node (ref "C17") (pin "1") (pinfunction "1_1") (pintype "passive"))
      (node (ref "C18") (pin "1") (pinfunction "1_1") (pintype "passive"))
      (node (ref "C19") (pin "1") (pinfunction "1_1") (pintype "passive"))
      (node (ref "C20") (pin "1") (pinfunction "1_1") (pintype "passive"))
      (node (ref "C21") (pin "1") (pinfunction "1_1") (pintype "passive"))
      (node (ref "C22") (pin "1") (pinfunction "1_1") (pintype "passive"))
      (node (ref "C23") (pin "1") (pinfunction "1_1") (pintype "passive"))
      (node (ref "C24") (pin "1") (pinfunction "1_1") (pintype "passive"))
      (node (ref "C25") (pin "1") (pinfunction "1_1") (pintype "passive"))
      (node (ref "C26") (pin "1") (pinfunction "1_1") (pintype "passive"))
      (node (ref "C27") (pin "1") (pinfunction "1_1") (pintype "passive"))
      (node (ref "C28") (pin "1") (pinfunction "1_1") (pintype "passive"))
      (node (ref "C29") (pin "1") (pinfunction "1_1") (pintype "passive"))
      (node (ref "C30") (pin "1") (pinfunction "1_1") (pintype "passive"))
      (node (ref "C8") (pin "1") (pinfunction "1_1") (pintype "passive"))
      (node (ref "C9") (pin "1") (pinfunction "1_1") (pintype "passive"))
    )
  )
)
